# BPF.net
KiCad netlist of a schematic drawn in Altium Designer
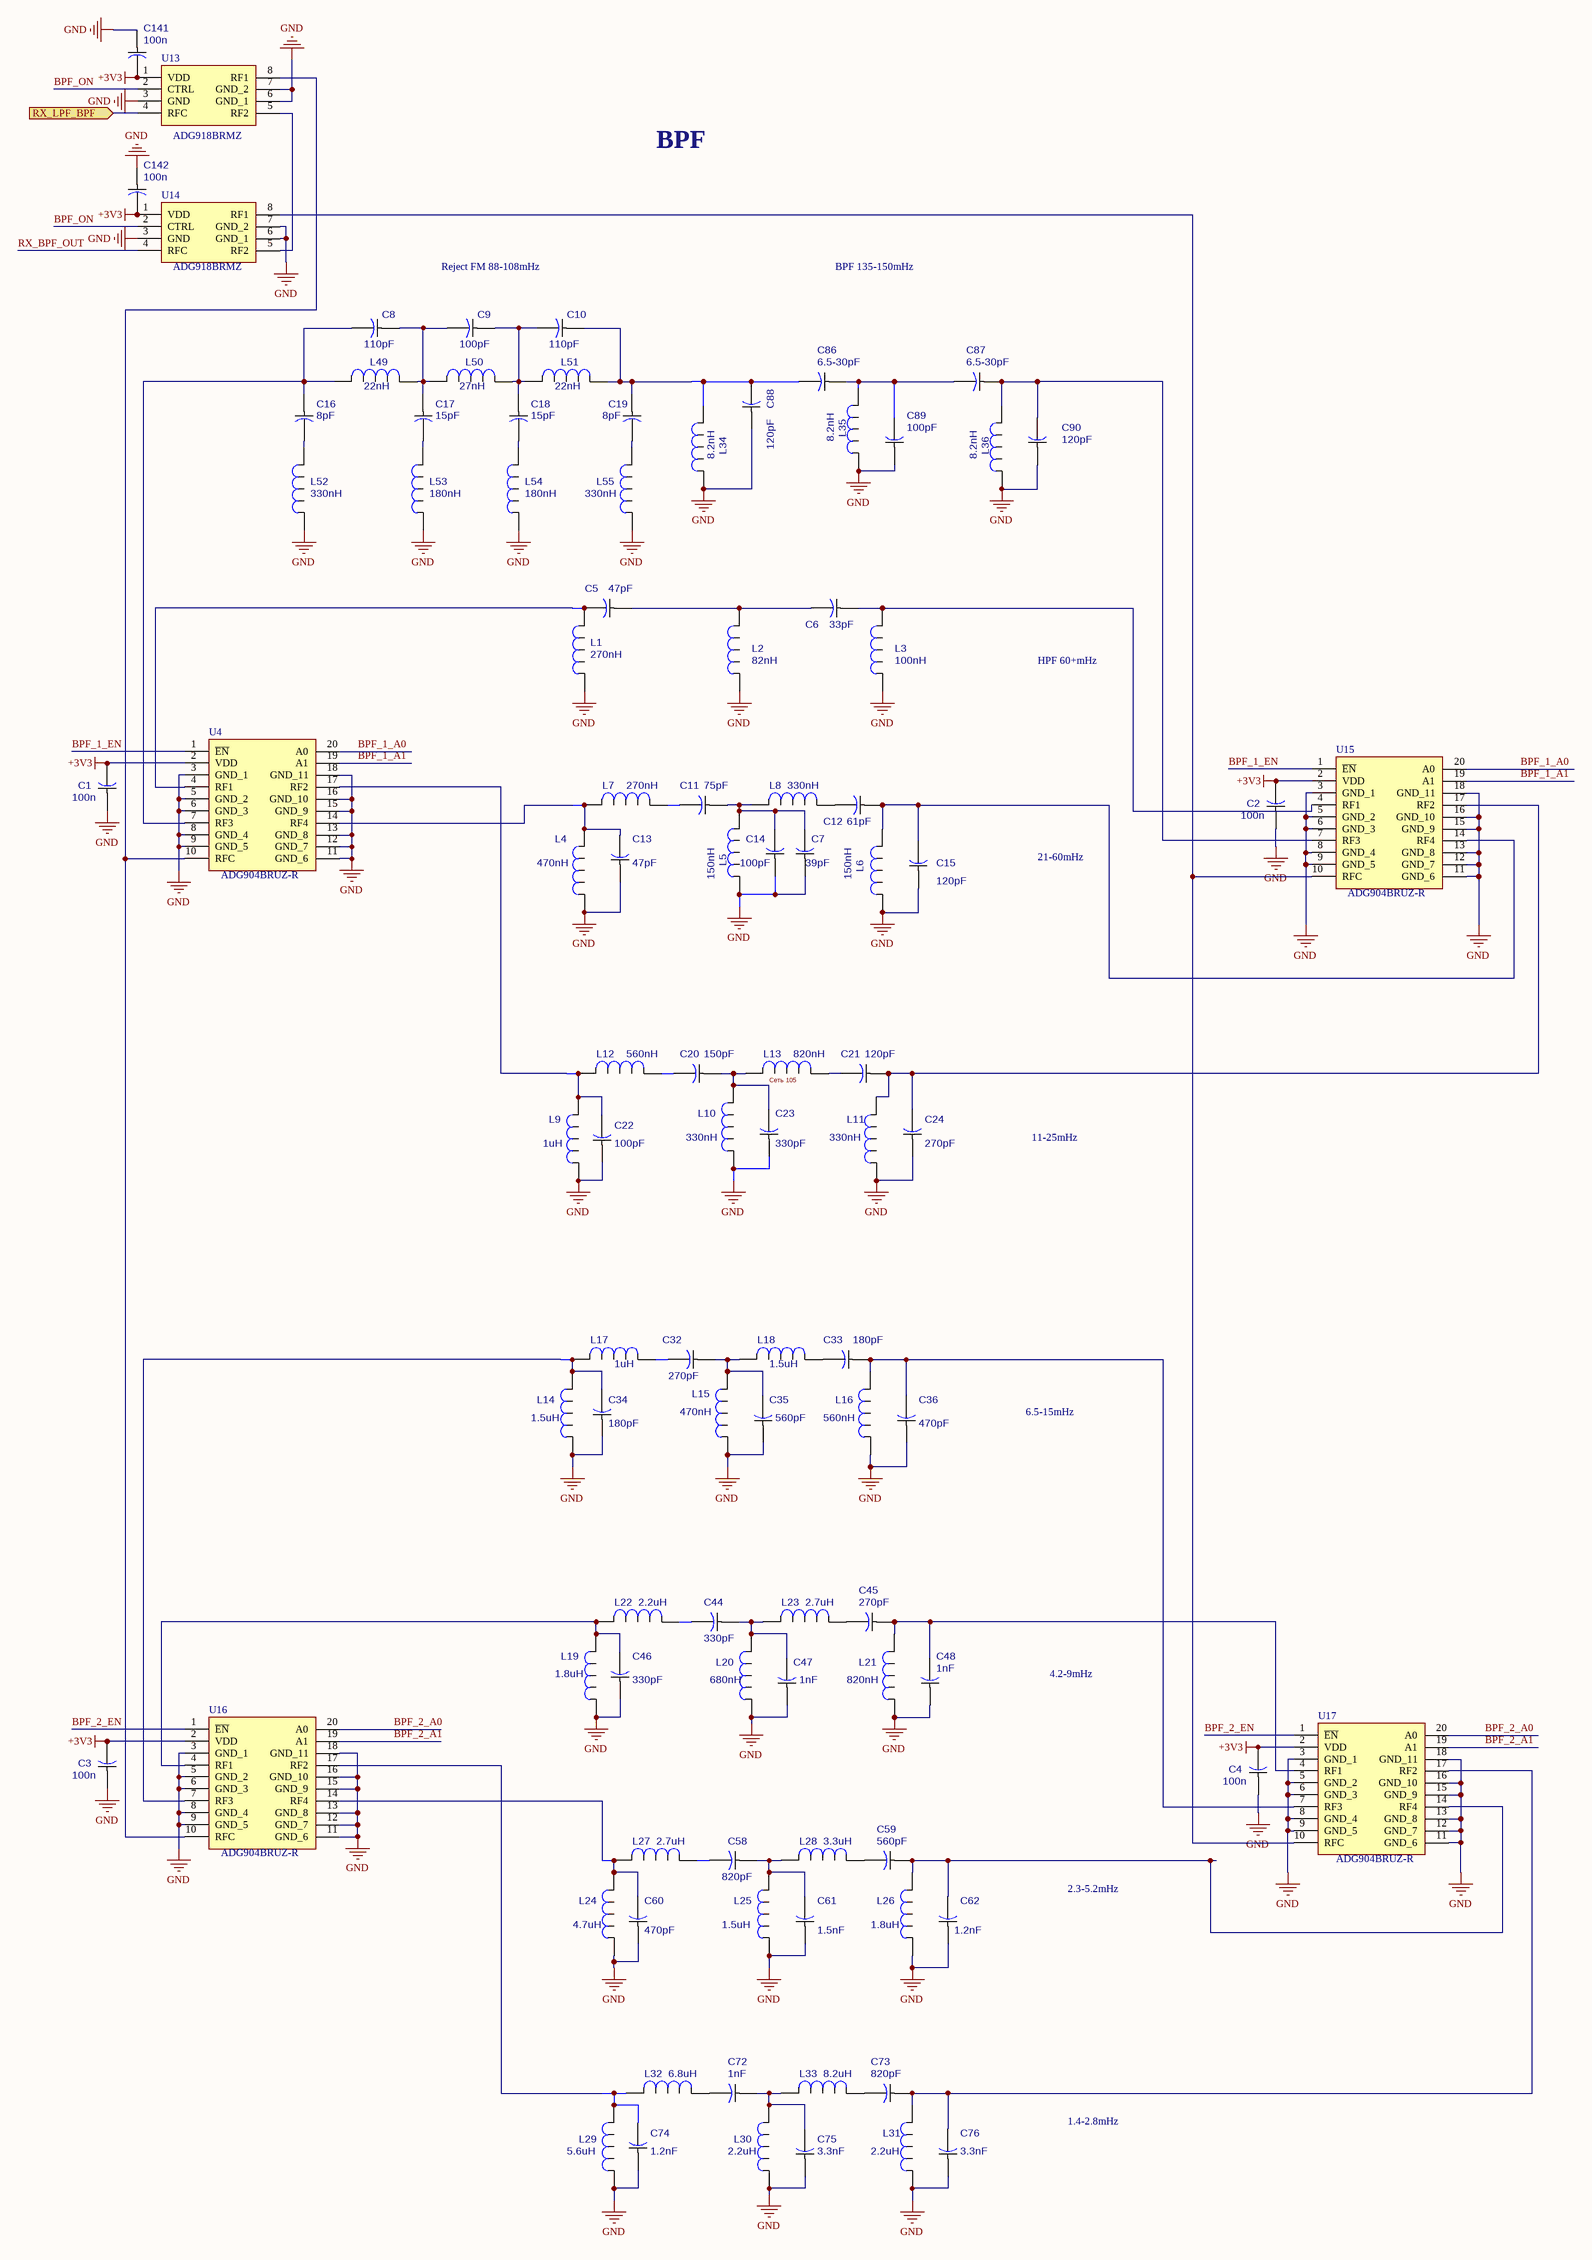
[diagram p0: BPF.SchDoc]

(export (version "E")
  (design (tool "Eeschema 10.0.6"))
  (components
    (comp (ref "C1")
      (value "100n")
      (footprint "CAP_0805")
      (description "CAP_0805")
      (libsource (lib "*") (part "CAP_0805"))
    )
    (comp (ref "C2")
      (value "100n")
      (footprint "CAP_0805")
      (description "CAP_0805")
      (libsource (lib "*") (part "CAP_0805"))
    )
    (comp (ref "C3")
      (value "100n")
      (footprint "CAP_0805")
      (description "CAP_0805")
      (libsource (lib "*") (part "CAP_0805"))
    )
    (comp (ref "C4")
      (value "100n")
      (footprint "CAP_0805")
      (description "CAP_0805")
      (libsource (lib "*") (part "CAP_0805"))
    )
    (comp (ref "C5")
      (value "47pF")
      (footprint "CAP_0805")
      (description "CAP_0805")
      (libsource (lib "*") (part "CAP_0805"))
    )
    (comp (ref "C6")
      (value "33pF")
      (footprint "CAP_0805")
      (description "CAP_0805")
      (libsource (lib "*") (part "CAP_0805"))
    )
    (comp (ref "C7")
      (value "39pF")
      (footprint "CAP_0805")
      (description "CAP_0805")
      (libsource (lib "*") (part "CAP_0805"))
    )
    (comp (ref "C8")
      (value "110pF")
      (footprint "CAP_0805")
      (description "CAP_0805")
      (libsource (lib "*") (part "CAP_0805"))
    )
    (comp (ref "C9")
      (value "100pF")
      (footprint "CAP_0805")
      (description "CAP_0805")
      (libsource (lib "*") (part "CAP_0805"))
    )
    (comp (ref "C10")
      (value "110pF")
      (footprint "CAP_0805")
      (description "CAP_0805")
      (libsource (lib "*") (part "CAP_0805"))
    )
    (comp (ref "C11")
      (value "75pF")
      (footprint "CAP_0805")
      (description "CAP_0805")
      (libsource (lib "*") (part "CAP_0805"))
    )
    (comp (ref "C12")
      (value "61pF")
      (footprint "CAP_0805")
      (description "CAP_0805")
      (libsource (lib "*") (part "CAP_0805"))
    )
    (comp (ref "C13")
      (value "47pF")
      (footprint "CAP_0805")
      (description "CAP_0805")
      (libsource (lib "*") (part "CAP_0805"))
    )
    (comp (ref "C14")
      (value "100pF")
      (footprint "CAP_0805")
      (description "CAP_0805")
      (libsource (lib "*") (part "CAP_0805"))
    )
    (comp (ref "C15")
      (value "120pF")
      (footprint "CAP_0805")
      (description "CAP_0805")
      (libsource (lib "*") (part "CAP_0805"))
    )
    (comp (ref "C16")
      (value "8pF")
      (footprint "CAP_0805")
      (description "CAP_0805")
      (libsource (lib "*") (part "CAP_0805"))
    )
    (comp (ref "C17")
      (value "15pF")
      (footprint "CAP_0805")
      (description "CAP_0805")
      (libsource (lib "*") (part "CAP_0805"))
    )
    (comp (ref "C18")
      (value "15pF")
      (footprint "CAP_0805")
      (description "CAP_0805")
      (libsource (lib "*") (part "CAP_0805"))
    )
    (comp (ref "C19")
      (value "8pF")
      (footprint "CAP_0805")
      (description "CAP_0805")
      (libsource (lib "*") (part "CAP_0805"))
    )
    (comp (ref "C20")
      (value "150pF")
      (footprint "CAP_0805")
      (description "CAP_0805")
      (libsource (lib "*") (part "CAP_0805"))
    )
    (comp (ref "C21")
      (value "120pF")
      (footprint "CAP_0805")
      (description "CAP_0805")
      (libsource (lib "*") (part "CAP_0805"))
    )
    (comp (ref "C22")
      (value "100pF")
      (footprint "CAP_0805")
      (description "CAP_0805")
      (libsource (lib "*") (part "CAP_0805"))
    )
    (comp (ref "C23")
      (value "330pF")
      (footprint "CAP_0805")
      (description "CAP_0805")
      (libsource (lib "*") (part "CAP_0805"))
    )
    (comp (ref "C24")
      (value "270pF")
      (footprint "CAP_0805")
      (description "CAP_0805")
      (libsource (lib "*") (part "CAP_0805"))
    )
    (comp (ref "C32")
      (value "270pF")
      (footprint "CAP_0805")
      (description "CAP_0805")
      (libsource (lib "*") (part "CAP_0805"))
    )
    (comp (ref "C33")
      (value "180pF")
      (footprint "CAP_0805")
      (description "CAP_0805")
      (libsource (lib "*") (part "CAP_0805"))
    )
    (comp (ref "C34")
      (value "180pF")
      (footprint "CAP_0805")
      (description "CAP_0805")
      (libsource (lib "*") (part "CAP_0805"))
    )
    (comp (ref "C35")
      (value "560pF")
      (footprint "CAP_0805")
      (description "CAP_0805")
      (libsource (lib "*") (part "CAP_0805"))
    )
    (comp (ref "C36")
      (value "470pF")
      (footprint "CAP_0805")
      (description "CAP_0805")
      (libsource (lib "*") (part "CAP_0805"))
    )
    (comp (ref "C44")
      (value "330pF")
      (footprint "CAP_0805")
      (description "CAP_0805")
      (libsource (lib "*") (part "CAP_0805"))
    )
    (comp (ref "C45")
      (value "270pF")
      (footprint "CAP_0805")
      (description "CAP_0805")
      (fields (field (name "Comment") "51pF"))
      (libsource (lib "*") (part "CAP_0805"))
    )
    (comp (ref "C46")
      (value "330pF")
      (footprint "CAP_0805")
      (description "CAP_0805")
      (libsource (lib "*") (part "CAP_0805"))
    )
    (comp (ref "C47")
      (value "1nF")
      (footprint "CAP_0805")
      (description "CAP_0805")
      (libsource (lib "*") (part "CAP_0805"))
    )
    (comp (ref "C48")
      (value "1nF")
      (footprint "CAP_0805")
      (description "CAP_0805")
      (libsource (lib "*") (part "CAP_0805"))
    )
    (comp (ref "C58")
      (value "820pF")
      (footprint "CAP_0805")
      (description "CAP_0805")
      (libsource (lib "*") (part "CAP_0805"))
    )
    (comp (ref "C59")
      (value "560pF")
      (footprint "CAP_0805")
      (description "CAP_0805")
      (fields (field (name "Comment") "680pF"))
      (libsource (lib "*") (part "CAP_0805"))
    )
    (comp (ref "C60")
      (value "470pF")
      (footprint "CAP_0805")
      (description "CAP_0805")
      (libsource (lib "*") (part "CAP_0805"))
    )
    (comp (ref "C61")
      (value "1.5nF")
      (footprint "CAP_0805")
      (description "CAP_0805")
      (libsource (lib "*") (part "CAP_0805"))
    )
    (comp (ref "C62")
      (value "1.2nF")
      (footprint "CAP_0805")
      (description "CAP_0805")
      (libsource (lib "*") (part "CAP_0805"))
    )
    (comp (ref "C72")
      (value "1nF")
      (footprint "CAP_0805")
      (description "CAP_0805")
      (libsource (lib "*") (part "CAP_0805"))
    )
    (comp (ref "C73")
      (value "820pF")
      (footprint "CAP_0805")
      (description "CAP_0805")
      (libsource (lib "*") (part "CAP_0805"))
    )
    (comp (ref "C74")
      (value "1.2nF")
      (footprint "CAP_0805")
      (description "CAP_0805")
      (libsource (lib "*") (part "CAP_0805"))
    )
    (comp (ref "C75")
      (value "3.3nF")
      (footprint "CAP_0805")
      (description "CAP_0805")
      (libsource (lib "*") (part "CAP_0805"))
    )
    (comp (ref "C76")
      (value "3.3nF")
      (footprint "CAP_0805")
      (description "CAP_0805")
      (libsource (lib "*") (part "CAP_0805"))
    )
    (comp (ref "C86")
      (value "6.5-30pF")
      (footprint "5025[2010]")
      (description "TZC3P300A110")
      (libsource (lib "*") (part "CAP_0805"))
    )
    (comp (ref "C87")
      (value "6.5-30pF")
      (footprint "5025[2010]")
      (description "TZC3P300A110")
      (libsource (lib "*") (part "CAP_0805"))
    )
    (comp (ref "C88")
      (value "120pF")
      (footprint "CAP_0805")
      (description "CAP_0805")
      (libsource (lib "*") (part "CAP_0805"))
    )
    (comp (ref "C89")
      (value "100pF")
      (footprint "CAP_0805")
      (description "CAP_0805")
      (libsource (lib "*") (part "CAP_0805"))
    )
    (comp (ref "C90")
      (value "120pF")
      (footprint "CAP_0805")
      (description "CAP_0805")
      (libsource (lib "*") (part "CAP_0805"))
    )
    (comp (ref "C141")
      (value "100n")
      (footprint "CAP_0805")
      (description "CAP_0805")
      (libsource (lib "*") (part "CAP_0805"))
    )
    (comp (ref "C142")
      (value "100n")
      (footprint "CAP_0805")
      (description "CAP_0805")
      (libsource (lib "*") (part "CAP_0805"))
    )
    (comp (ref "L1")
      (value "270nH")
      (footprint "IND_0805")
      (description "IND_0805")
      (libsource (lib "*") (part "IND_0805"))
    )
    (comp (ref "L2")
      (value "82nH")
      (footprint "IND_0805")
      (description "IND_0805")
      (libsource (lib "*") (part "IND_0805"))
    )
    (comp (ref "L3")
      (value "100nH")
      (footprint "IND_0805")
      (description "IND_0805")
      (libsource (lib "*") (part "IND_0805"))
    )
    (comp (ref "L4")
      (value "470nH")
      (footprint "IND_0805")
      (description "IND_0805")
      (libsource (lib "*") (part "IND_0805"))
    )
    (comp (ref "L5")
      (value "150nH")
      (footprint "IND_0805")
      (description "IND_0805")
      (libsource (lib "*") (part "IND_0805"))
    )
    (comp (ref "L6")
      (value "150nH")
      (footprint "IND_0805")
      (description "IND_0805")
      (libsource (lib "*") (part "IND_0805"))
    )
    (comp (ref "L7")
      (value "270nH")
      (footprint "IND_0805")
      (description "IND_0805")
      (libsource (lib "*") (part "IND_0805"))
    )
    (comp (ref "L8")
      (value "330nH")
      (footprint "IND_0805")
      (description "IND_0805")
      (libsource (lib "*") (part "IND_0805"))
    )
    (comp (ref "L9")
      (value "1uH")
      (footprint "IND_0805")
      (description "IND_0805")
      (libsource (lib "*") (part "IND_0805"))
    )
    (comp (ref "L10")
      (value "330nH")
      (footprint "IND_0805")
      (description "IND_0805")
      (libsource (lib "*") (part "IND_0805"))
    )
    (comp (ref "L11")
      (value "330nH")
      (footprint "IND_0805")
      (description "IND_0805")
      (libsource (lib "*") (part "IND_0805"))
    )
    (comp (ref "L12")
      (value "560nH")
      (footprint "IND_0805")
      (description "IND_0805")
      (libsource (lib "*") (part "IND_0805"))
    )
    (comp (ref "L13")
      (value "820nH")
      (footprint "IND_0805")
      (description "IND_0805")
      (libsource (lib "*") (part "IND_0805"))
    )
    (comp (ref "L14")
      (value "1.5uH")
      (footprint "IND_0805")
      (description "IND_0805")
      (libsource (lib "*") (part "IND_0805"))
    )
    (comp (ref "L15")
      (value "470nH")
      (footprint "IND_0805")
      (description "IND_0805")
      (libsource (lib "*") (part "IND_0805"))
    )
    (comp (ref "L16")
      (value "560nH")
      (footprint "IND_0805")
      (description "IND_0805")
      (libsource (lib "*") (part "IND_0805"))
    )
    (comp (ref "L17")
      (value "1uH")
      (footprint "IND_0805")
      (description "IND_0805")
      (libsource (lib "*") (part "IND_0805"))
    )
    (comp (ref "L18")
      (value "1.5uH")
      (footprint "IND_0805")
      (description "IND_0805")
      (libsource (lib "*") (part "IND_0805"))
    )
    (comp (ref "L19")
      (value "1.8uH")
      (footprint "IND_0805")
      (description "IND_0805")
      (libsource (lib "*") (part "IND_0805"))
    )
    (comp (ref "L20")
      (value "680nH")
      (footprint "IND_0805")
      (description "IND_0805")
      (libsource (lib "*") (part "IND_0805"))
    )
    (comp (ref "L21")
      (value "820nH")
      (footprint "IND_0805")
      (description "IND_0805")
      (libsource (lib "*") (part "IND_0805"))
    )
    (comp (ref "L22")
      (value "2.2uH")
      (footprint "IND_0805")
      (description "IND_0805")
      (libsource (lib "*") (part "IND_0805"))
    )
    (comp (ref "L23")
      (value "2.7uH")
      (footprint "IND_0805")
      (description "IND_0805")
      (libsource (lib "*") (part "IND_0805"))
    )
    (comp (ref "L24")
      (value "4.7uH")
      (footprint "IND_0805")
      (description "IND_0805")
      (libsource (lib "*") (part "IND_0805"))
    )
    (comp (ref "L25")
      (value "1.5uH")
      (footprint "IND_0805")
      (description "IND_0805")
      (libsource (lib "*") (part "IND_0805"))
    )
    (comp (ref "L26")
      (value "1.8uH")
      (footprint "IND_0805")
      (description "IND_0805")
      (libsource (lib "*") (part "IND_0805"))
    )
    (comp (ref "L27")
      (value "2.7uH")
      (footprint "IND_0805")
      (description "IND_0805")
      (libsource (lib "*") (part "IND_0805"))
    )
    (comp (ref "L28")
      (value "3.3uH")
      (footprint "IND_0805")
      (description "IND_0805")
      (libsource (lib "*") (part "IND_0805"))
    )
    (comp (ref "L29")
      (value "5.6uH")
      (footprint "IND_0805")
      (description "IND_0805")
      (libsource (lib "*") (part "IND_0805"))
    )
    (comp (ref "L30")
      (value "2.2uH")
      (footprint "IND_0805")
      (description "IND_0805")
      (libsource (lib "*") (part "IND_0805"))
    )
    (comp (ref "L31")
      (value "2.2uH")
      (footprint "IND_0805")
      (description "IND_0805")
      (libsource (lib "*") (part "IND_0805"))
    )
    (comp (ref "L32")
      (value "6.8uH")
      (footprint "IND_0805")
      (description "IND_0805")
      (libsource (lib "*") (part "IND_0805"))
    )
    (comp (ref "L33")
      (value "8.2uH")
      (footprint "IND_0805")
      (description "IND_0805")
      (libsource (lib "*") (part "IND_0805"))
    )
    (comp (ref "L34")
      (value "8.2nH")
      (footprint "IND_0805")
      (description "IND_0805")
      (libsource (lib "*") (part "IND_0805"))
    )
    (comp (ref "L35")
      (value "8.2nH")
      (footprint "IND_0805")
      (description "IND_0805")
      (libsource (lib "*") (part "IND_0805"))
    )
    (comp (ref "L36")
      (value "8.2nH")
      (footprint "IND_0805")
      (description "IND_0805")
      (libsource (lib "*") (part "IND_0805"))
    )
    (comp (ref "L49")
      (value "22nH")
      (footprint "IND_0805")
      (description "IND_0805")
      (libsource (lib "*") (part "IND_0805"))
    )
    (comp (ref "L50")
      (value "27nH")
      (footprint "IND_0805")
      (description "IND_0805")
      (libsource (lib "*") (part "IND_0805"))
    )
    (comp (ref "L51")
      (value "22nH")
      (footprint "IND_0805")
      (description "IND_0805")
      (libsource (lib "*") (part "IND_0805"))
    )
    (comp (ref "L52")
      (value "330nH")
      (footprint "IND_0805")
      (description "IND_0805")
      (libsource (lib "*") (part "IND_0805"))
    )
    (comp (ref "L53")
      (value "180nH")
      (footprint "IND_0805")
      (description "IND_0805")
      (libsource (lib "*") (part "IND_0805"))
    )
    (comp (ref "L54")
      (value "180nH")
      (footprint "IND_0805")
      (description "IND_0805")
      (libsource (lib "*") (part "IND_0805"))
    )
    (comp (ref "L55")
      (value "330nH")
      (footprint "IND_0805")
      (description "IND_0805")
      (libsource (lib "*") (part "IND_0805"))
    )
    (comp (ref "U4")
      (value "ADG904BRUZ-R")
      (footprint "SamacSys:SOP65P640X120-20N")
      (description "Integrated Circuit")
      (fields
        (field (name "MOUSER PART NUMBER") "584-ADG904BRUZ-R")
        (field (name "RS PART NUMBER") "5385019P")
      )
      (libsource (lib "*") (part "ADG904BRUZ-R"))
    )
    (comp (ref "U13")
      (value "ADG918BRMZ")
      (footprint "SamacSys:SOP65P490X110-8N")
      (description "Integrated Circuit")
      (fields (field (name "MOUSER PART NUMBER") "584-ADG918BRMZ") (field (name "RS PART NUMBER") "4969212P"))
      (libsource (lib "*") (part "ADG918BRMZ"))
    )
    (comp (ref "U14")
      (value "ADG918BRMZ")
      (footprint "SamacSys:SOP65P490X110-8N")
      (description "Integrated Circuit")
      (fields (field (name "MOUSER PART NUMBER") "584-ADG918BRMZ") (field (name "RS PART NUMBER") "4969212P"))
      (libsource (lib "*") (part "ADG918BRMZ"))
    )
    (comp (ref "U15")
      (value "ADG904BRUZ-R")
      (footprint "SamacSys:SOP65P640X120-20N")
      (description "Integrated Circuit")
      (fields
        (field (name "MOUSER PART NUMBER") "584-ADG904BRUZ-R")
        (field (name "RS PART NUMBER") "5385019P")
      )
      (libsource (lib "*") (part "ADG904BRUZ-R"))
    )
    (comp (ref "U16")
      (value "ADG904BRUZ-R")
      (footprint "SamacSys:SOP65P640X120-20N")
      (description "Integrated Circuit")
      (fields
        (field (name "MOUSER PART NUMBER") "584-ADG904BRUZ-R")
        (field (name "RS PART NUMBER") "5385019P")
      )
      (libsource (lib "*") (part "ADG904BRUZ-R"))
    )
    (comp (ref "U17")
      (value "ADG904BRUZ-R")
      (footprint "SamacSys:SOP65P640X120-20N")
      (description "Integrated Circuit")
      (fields
        (field (name "MOUSER PART NUMBER") "584-ADG904BRUZ-R")
        (field (name "RS PART NUMBER") "5385019P")
      )
      (libsource (lib "*") (part "ADG904BRUZ-R"))
    )
  )
  (nets
    (net (code "1") (name "+3V3") (class "Default")
      (node (ref "C1") (pin "2") (pinfunction "2_2") (pintype "passive"))
      (node (ref "C141") (pin "2") (pinfunction "2_2") (pintype "passive"))
      (node (ref "C142") (pin "2") (pinfunction "2_2") (pintype "passive"))
      (node (ref "C2") (pin "2") (pinfunction "2_2") (pintype "passive"))
      (node (ref "C3") (pin "2") (pinfunction "2_2") (pintype "passive"))
      (node (ref "C4") (pin "2") (pinfunction "2_2") (pintype "passive"))
      (node (ref "U13") (pin "1") (pinfunction "VDD_1") (pintype "power_in"))
      (node (ref "U14") (pin "1") (pinfunction "VDD_1") (pintype "power_in"))
      (node (ref "U15") (pin "2") (pinfunction "VDD_2") (pintype "passive"))
      (node (ref "U16") (pin "2") (pinfunction "VDD_2") (pintype "passive"))
      (node (ref "U17") (pin "2") (pinfunction "VDD_2") (pintype "passive"))
      (node (ref "U4") (pin "2") (pinfunction "VDD_2") (pintype "passive"))
    )
    (net (code "2") (name "/BPF_1_A0") (class "Default")
      (node (ref "U15") (pin "20") (pinfunction "A0_20") (pintype "passive"))
      (node (ref "U4") (pin "20") (pinfunction "A0_20") (pintype "passive"))
    )
    (net (code "3") (name "/BPF_1_A1") (class "Default")
      (node (ref "U15") (pin "19") (pinfunction "A1_19") (pintype "passive"))
      (node (ref "U4") (pin "19") (pinfunction "A1_19") (pintype "passive"))
    )
    (net (code "4") (name "/BPF_1_EN") (class "Default")
      (node (ref "U15") (pin "1") (pinfunction "~{EN}_1") (pintype "passive"))
      (node (ref "U4") (pin "1") (pinfunction "~{EN}_1") (pintype "passive"))
    )
    (net (code "5") (name "/BPF_2_A0") (class "Default")
      (node (ref "U16") (pin "20") (pinfunction "A0_20") (pintype "passive"))
      (node (ref "U17") (pin "20") (pinfunction "A0_20") (pintype "passive"))
    )
    (net (code "6") (name "/BPF_2_A1") (class "Default")
      (node (ref "U16") (pin "19") (pinfunction "A1_19") (pintype "passive"))
      (node (ref "U17") (pin "19") (pinfunction "A1_19") (pintype "passive"))
    )
    (net (code "7") (name "/BPF_2_EN") (class "Default")
      (node (ref "U16") (pin "1") (pinfunction "~{EN}_1") (pintype "passive"))
      (node (ref "U17") (pin "1") (pinfunction "~{EN}_1") (pintype "passive"))
    )
    (net (code "8") (name "/BPF_ON") (class "Default")
      (node (ref "U13") (pin "2") (pinfunction "CTRL_2") (pintype "passive"))
      (node (ref "U14") (pin "2") (pinfunction "CTRL_2") (pintype "passive"))
    )
    (net (code "9") (name "/RX_BPF_OUT") (class "Default")
      (node (ref "U14") (pin "4") (pinfunction "RFC_4") (pintype "passive"))
    )
    (net (code "10") (name "/RX_LPF_BPF") (class "Default")
      (node (ref "U13") (pin "4") (pinfunction "RFC_4") (pintype "passive"))
    )
    (net (code "11") (name "/Сеть 105") (class "Default")
      (node (ref "C20") (pin "1") (pinfunction "1_1") (pintype "passive"))
      (node (ref "C23") (pin "2") (pinfunction "2_2") (pintype "passive"))
      (node (ref "L10") (pin "2") (pinfunction "2_2") (pintype "passive"))
      (node (ref "L13") (pin "1") (pinfunction "1_1") (pintype "passive"))
    )
    (net (code "12") (name "GND") (class "Default")
      (node (ref "C1") (pin "1") (pinfunction "1_1") (pintype "passive"))
      (node (ref "C13") (pin "1") (pinfunction "1_1") (pintype "passive"))
      (node (ref "C14") (pin "1") (pinfunction "1_1") (pintype "passive"))
      (node (ref "C141") (pin "1") (pinfunction "1_1") (pintype "passive"))
      (node (ref "C142") (pin "1") (pinfunction "1_1") (pintype "passive"))
      (node (ref "C15") (pin "1") (pinfunction "1_1") (pintype "passive"))
      (node (ref "C2") (pin "1") (pinfunction "1_1") (pintype "passive"))
      (node (ref "C22") (pin "1") (pinfunction "1_1") (pintype "passive"))
      (node (ref "C23") (pin "1") (pinfunction "1_1") (pintype "passive"))
      (node (ref "C24") (pin "1") (pinfunction "1_1") (pintype "passive"))
      (node (ref "C3") (pin "1") (pinfunction "1_1") (pintype "passive"))
      (node (ref "C34") (pin "1") (pinfunction "1_1") (pintype "passive"))
      (node (ref "C35") (pin "1") (pinfunction "1_1") (pintype "passive"))
      (node (ref "C36") (pin "1") (pinfunction "1_1") (pintype "passive"))
      (node (ref "C4") (pin "1") (pinfunction "1_1") (pintype "passive"))
      (node (ref "C46") (pin "1") (pinfunction "1_1") (pintype "passive"))
      (node (ref "C47") (pin "1") (pinfunction "1_1") (pintype "passive"))
      (node (ref "C48") (pin "1") (pinfunction "1_1") (pintype "passive"))
      (node (ref "C60") (pin "1") (pinfunction "1_1") (pintype "passive"))
      (node (ref "C61") (pin "1") (pinfunction "1_1") (pintype "passive"))
      (node (ref "C62") (pin "1") (pinfunction "1_1") (pintype "passive"))
      (node (ref "C7") (pin "1") (pinfunction "1_1") (pintype "passive"))
      (node (ref "C74") (pin "1") (pinfunction "1_1") (pintype "passive"))
      (node (ref "C75") (pin "1") (pinfunction "1_1") (pintype "passive"))
      (node (ref "C76") (pin "1") (pinfunction "1_1") (pintype "passive"))
      (node (ref "C88") (pin "1") (pinfunction "1_1") (pintype "passive"))
      (node (ref "C89") (pin "1") (pinfunction "1_1") (pintype "passive"))
      (node (ref "C90") (pin "1") (pinfunction "1_1") (pintype "passive"))
      (node (ref "L1") (pin "1") (pinfunction "1_1") (pintype "passive"))
      (node (ref "L10") (pin "1") (pinfunction "1_1") (pintype "passive"))
      (node (ref "L11") (pin "1") (pinfunction "1_1") (pintype "passive"))
      (node (ref "L14") (pin "1") (pinfunction "1_1") (pintype "passive"))
      (node (ref "L15") (pin "1") (pinfunction "1_1") (pintype "passive"))
      (node (ref "L16") (pin "1") (pinfunction "1_1") (pintype "passive"))
      (node (ref "L19") (pin "1") (pinfunction "1_1") (pintype "passive"))
      (node (ref "L2") (pin "1") (pinfunction "1_1") (pintype "passive"))
      (node (ref "L20") (pin "1") (pinfunction "1_1") (pintype "passive"))
      (node (ref "L21") (pin "1") (pinfunction "1_1") (pintype "passive"))
      (node (ref "L24") (pin "1") (pinfunction "1_1") (pintype "passive"))
      (node (ref "L25") (pin "1") (pinfunction "1_1") (pintype "passive"))
      (node (ref "L26") (pin "1") (pinfunction "1_1") (pintype "passive"))
      (node (ref "L29") (pin "1") (pinfunction "1_1") (pintype "passive"))
      (node (ref "L3") (pin "1") (pinfunction "1_1") (pintype "passive"))
      (node (ref "L30") (pin "1") (pinfunction "1_1") (pintype "passive"))
      (node (ref "L31") (pin "1") (pinfunction "1_1") (pintype "passive"))
      (node (ref "L34") (pin "1") (pinfunction "1_1") (pintype "passive"))
      (node (ref "L35") (pin "1") (pinfunction "1_1") (pintype "passive"))
      (node (ref "L36") (pin "1") (pinfunction "1_1") (pintype "passive"))
      (node (ref "L4") (pin "1") (pinfunction "1_1") (pintype "passive"))
      (node (ref "L5") (pin "1") (pinfunction "1_1") (pintype "passive"))
      (node (ref "L52") (pin "1") (pinfunction "1_1") (pintype "passive"))
      (node (ref "L53") (pin "1") (pinfunction "1_1") (pintype "passive"))
      (node (ref "L54") (pin "1") (pinfunction "1_1") (pintype "passive"))
      (node (ref "L55") (pin "1") (pinfunction "1_1") (pintype "passive"))
      (node (ref "L6") (pin "1") (pinfunction "1_1") (pintype "passive"))
      (node (ref "L9") (pin "1") (pinfunction "1_1") (pintype "passive"))
      (node (ref "U13") (pin "3") (pinfunction "GND_3") (pintype "power_in"))
      (node (ref "U13") (pin "6") (pinfunction "GND_1_6") (pintype "power_in"))
      (node (ref "U13") (pin "7") (pinfunction "GND_2_7") (pintype "power_in"))
      (node (ref "U14") (pin "3") (pinfunction "GND_3") (pintype "power_in"))
      (node (ref "U14") (pin "6") (pinfunction "GND_1_6") (pintype "power_in"))
      (node (ref "U14") (pin "7") (pinfunction "GND_2_7") (pintype "power_in"))
      (node (ref "U15") (pin "11") (pinfunction "GND_6_11") (pintype "passive"))
      (node (ref "U15") (pin "12") (pinfunction "GND_7_12") (pintype "passive"))
      (node (ref "U15") (pin "13") (pinfunction "GND_8_13") (pintype "passive"))
      (node (ref "U15") (pin "15") (pinfunction "GND_9_15") (pintype "passive"))
      (node (ref "U15") (pin "16") (pinfunction "GND_10_16") (pintype "passive"))
      (node (ref "U15") (pin "18") (pinfunction "GND_11_18") (pintype "passive"))
      (node (ref "U15") (pin "3") (pinfunction "GND_1_3") (pintype "passive"))
      (node (ref "U15") (pin "5") (pinfunction "GND_2_5") (pintype "passive"))
      (node (ref "U15") (pin "6") (pinfunction "GND_3_6") (pintype "passive"))
      (node (ref "U15") (pin "8") (pinfunction "GND_4_8") (pintype "passive"))
      (node (ref "U15") (pin "9") (pinfunction "GND_5_9") (pintype "passive"))
      (node (ref "U16") (pin "11") (pinfunction "GND_6_11") (pintype "passive"))
      (node (ref "U16") (pin "12") (pinfunction "GND_7_12") (pintype "passive"))
      (node (ref "U16") (pin "13") (pinfunction "GND_8_13") (pintype "passive"))
      (node (ref "U16") (pin "15") (pinfunction "GND_9_15") (pintype "passive"))
      (node (ref "U16") (pin "16") (pinfunction "GND_10_16") (pintype "passive"))
      (node (ref "U16") (pin "18") (pinfunction "GND_11_18") (pintype "passive"))
      (node (ref "U16") (pin "3") (pinfunction "GND_1_3") (pintype "passive"))
      (node (ref "U16") (pin "5") (pinfunction "GND_2_5") (pintype "passive"))
      (node (ref "U16") (pin "6") (pinfunction "GND_3_6") (pintype "passive"))
      (node (ref "U16") (pin "8") (pinfunction "GND_4_8") (pintype "passive"))
      (node (ref "U16") (pin "9") (pinfunction "GND_5_9") (pintype "passive"))
      (node (ref "U17") (pin "11") (pinfunction "GND_6_11") (pintype "passive"))
      (node (ref "U17") (pin "12") (pinfunction "GND_7_12") (pintype "passive"))
      (node (ref "U17") (pin "13") (pinfunction "GND_8_13") (pintype "passive"))
      (node (ref "U17") (pin "15") (pinfunction "GND_9_15") (pintype "passive"))
      (node (ref "U17") (pin "16") (pinfunction "GND_10_16") (pintype "passive"))
      (node (ref "U17") (pin "18") (pinfunction "GND_11_18") (pintype "passive"))
      (node (ref "U17") (pin "3") (pinfunction "GND_1_3") (pintype "passive"))
      (node (ref "U17") (pin "5") (pinfunction "GND_2_5") (pintype "passive"))
      (node (ref "U17") (pin "6") (pinfunction "GND_3_6") (pintype "passive"))
      (node (ref "U17") (pin "8") (pinfunction "GND_4_8") (pintype "passive"))
      (node (ref "U17") (pin "9") (pinfunction "GND_5_9") (pintype "passive"))
      (node (ref "U4") (pin "11") (pinfunction "GND_6_11") (pintype "passive"))
      (node (ref "U4") (pin "12") (pinfunction "GND_7_12") (pintype "passive"))
      (node (ref "U4") (pin "13") (pinfunction "GND_8_13") (pintype "passive"))
      (node (ref "U4") (pin "15") (pinfunction "GND_9_15") (pintype "passive"))
      (node (ref "U4") (pin "16") (pinfunction "GND_10_16") (pintype "passive"))
      (node (ref "U4") (pin "18") (pinfunction "GND_11_18") (pintype "passive"))
      (node (ref "U4") (pin "3") (pinfunction "GND_1_3") (pintype "passive"))
      (node (ref "U4") (pin "5") (pinfunction "GND_2_5") (pintype "passive"))
      (node (ref "U4") (pin "6") (pinfunction "GND_3_6") (pintype "passive"))
      (node (ref "U4") (pin "8") (pinfunction "GND_4_8") (pintype "passive"))
      (node (ref "U4") (pin "9") (pinfunction "GND_5_9") (pintype "passive"))
    )
    (net (code "13") (name "Net-(C5-Pad1)") (class "Default")
      (node (ref "C5") (pin "1") (pinfunction "1_1") (pintype "passive"))
      (node (ref "C6") (pin "2") (pinfunction "2_2") (pintype "passive"))
      (node (ref "L2") (pin "2") (pinfunction "2_2") (pintype "passive"))
    )
    (net (code "14") (name "Net-(C10-Pad1)") (class "Default")
      (node (ref "C10") (pin "1") (pinfunction "1_1") (pintype "passive"))
      (node (ref "C19") (pin "1") (pinfunction "1_1") (pintype "passive"))
      (node (ref "C86") (pin "2") (pinfunction "2_2") (pintype "passive"))
      (node (ref "C88") (pin "2") (pinfunction "2_2") (pintype "passive"))
      (node (ref "L34") (pin "2") (pinfunction "2_2") (pintype "passive"))
      (node (ref "L51") (pin "2") (pinfunction "2_2") (pintype "passive"))
    )
    (net (code "15") (name "Net-(C10-Pad2)") (class "Default")
      (node (ref "C10") (pin "2") (pinfunction "2_2") (pintype "passive"))
      (node (ref "C18") (pin "1") (pinfunction "1_1") (pintype "passive"))
      (node (ref "C9") (pin "1") (pinfunction "1_1") (pintype "passive"))
      (node (ref "L50") (pin "2") (pinfunction "2_2") (pintype "passive"))
      (node (ref "L51") (pin "1") (pinfunction "1_1") (pintype "passive"))
    )
    (net (code "16") (name "Net-(C11-Pad1)") (class "Default")
      (node (ref "C11") (pin "1") (pinfunction "1_1") (pintype "passive"))
      (node (ref "C14") (pin "2") (pinfunction "2_2") (pintype "passive"))
      (node (ref "C7") (pin "2") (pinfunction "2_2") (pintype "passive"))
      (node (ref "L5") (pin "2") (pinfunction "2_2") (pintype "passive"))
      (node (ref "L8") (pin "1") (pinfunction "1_1") (pintype "passive"))
    )
    (net (code "17") (name "Net-(C11-Pad2)") (class "Default")
      (node (ref "C11") (pin "2") (pinfunction "2_2") (pintype "passive"))
      (node (ref "L7") (pin "2") (pinfunction "2_2") (pintype "passive"))
    )
    (net (code "18") (name "Net-(C12-Pad2)") (class "Default")
      (node (ref "C12") (pin "2") (pinfunction "2_2") (pintype "passive"))
      (node (ref "L8") (pin "2") (pinfunction "2_2") (pintype "passive"))
    )
    (net (code "19") (name "Net-(C16-Pad2)") (class "Default")
      (node (ref "C16") (pin "2") (pinfunction "2_2") (pintype "passive"))
      (node (ref "L52") (pin "2") (pinfunction "2_2") (pintype "passive"))
    )
    (net (code "20") (name "Net-(C17-Pad1)") (class "Default")
      (node (ref "C17") (pin "1") (pinfunction "1_1") (pintype "passive"))
      (node (ref "C8") (pin "1") (pinfunction "1_1") (pintype "passive"))
      (node (ref "C9") (pin "2") (pinfunction "2_2") (pintype "passive"))
      (node (ref "L49") (pin "2") (pinfunction "2_2") (pintype "passive"))
      (node (ref "L50") (pin "1") (pinfunction "1_1") (pintype "passive"))
    )
    (net (code "21") (name "Net-(C17-Pad2)") (class "Default")
      (node (ref "C17") (pin "2") (pinfunction "2_2") (pintype "passive"))
      (node (ref "L53") (pin "2") (pinfunction "2_2") (pintype "passive"))
    )
    (net (code "22") (name "Net-(C18-Pad2)") (class "Default")
      (node (ref "C18") (pin "2") (pinfunction "2_2") (pintype "passive"))
      (node (ref "L54") (pin "2") (pinfunction "2_2") (pintype "passive"))
    )
    (net (code "23") (name "Net-(C19-Pad2)") (class "Default")
      (node (ref "C19") (pin "2") (pinfunction "2_2") (pintype "passive"))
      (node (ref "L55") (pin "2") (pinfunction "2_2") (pintype "passive"))
    )
    (net (code "24") (name "Net-(C20-Pad2)") (class "Default")
      (node (ref "C20") (pin "2") (pinfunction "2_2") (pintype "passive"))
      (node (ref "L12") (pin "2") (pinfunction "2_2") (pintype "passive"))
    )
    (net (code "25") (name "Net-(C21-Pad2)") (class "Default")
      (node (ref "C21") (pin "2") (pinfunction "2_2") (pintype "passive"))
      (node (ref "L13") (pin "2") (pinfunction "2_2") (pintype "passive"))
    )
    (net (code "26") (name "Net-(C32-Pad1)") (class "Default")
      (node (ref "C32") (pin "1") (pinfunction "1_1") (pintype "passive"))
      (node (ref "C35") (pin "2") (pinfunction "2_2") (pintype "passive"))
      (node (ref "L15") (pin "2") (pinfunction "2_2") (pintype "passive"))
      (node (ref "L18") (pin "1") (pinfunction "1_1") (pintype "passive"))
    )
    (net (code "27") (name "Net-(C32-Pad2)") (class "Default")
      (node (ref "C32") (pin "2") (pinfunction "2_2") (pintype "passive"))
      (node (ref "L17") (pin "2") (pinfunction "2_2") (pintype "passive"))
    )
    (net (code "28") (name "Net-(C33-Pad2)") (class "Default")
      (node (ref "C33") (pin "2") (pinfunction "2_2") (pintype "passive"))
      (node (ref "L18") (pin "2") (pinfunction "2_2") (pintype "passive"))
    )
    (net (code "29") (name "Net-(C44-Pad1)") (class "Default")
      (node (ref "C44") (pin "1") (pinfunction "1_1") (pintype "passive"))
      (node (ref "C47") (pin "2") (pinfunction "2_2") (pintype "passive"))
      (node (ref "L20") (pin "2") (pinfunction "2_2") (pintype "passive"))
      (node (ref "L23") (pin "1") (pinfunction "1_1") (pintype "passive"))
    )
    (net (code "30") (name "Net-(C44-Pad2)") (class "Default")
      (node (ref "C44") (pin "2") (pinfunction "2_2") (pintype "passive"))
      (node (ref "L22") (pin "2") (pinfunction "2_2") (pintype "passive"))
    )
    (net (code "31") (name "Net-(C45-Pad2)") (class "Default")
      (node (ref "C45") (pin "2") (pinfunction "2_2") (pintype "passive"))
      (node (ref "L23") (pin "2") (pinfunction "2_2") (pintype "passive"))
    )
    (net (code "32") (name "Net-(C58-Pad1)") (class "Default")
      (node (ref "C58") (pin "1") (pinfunction "1_1") (pintype "passive"))
      (node (ref "C61") (pin "2") (pinfunction "2_2") (pintype "passive"))
      (node (ref "L25") (pin "2") (pinfunction "2_2") (pintype "passive"))
      (node (ref "L28") (pin "1") (pinfunction "1_1") (pintype "passive"))
    )
    (net (code "33") (name "Net-(C58-Pad2)") (class "Default")
      (node (ref "C58") (pin "2") (pinfunction "2_2") (pintype "passive"))
      (node (ref "L27") (pin "2") (pinfunction "2_2") (pintype "passive"))
    )
    (net (code "34") (name "Net-(C59-Pad2)") (class "Default")
      (node (ref "C59") (pin "2") (pinfunction "2_2") (pintype "passive"))
      (node (ref "L28") (pin "2") (pinfunction "2_2") (pintype "passive"))
    )
    (net (code "35") (name "Net-(C72-Pad1)") (class "Default")
      (node (ref "C72") (pin "1") (pinfunction "1_1") (pintype "passive"))
      (node (ref "C75") (pin "2") (pinfunction "2_2") (pintype "passive"))
      (node (ref "L30") (pin "2") (pinfunction "2_2") (pintype "passive"))
      (node (ref "L33") (pin "1") (pinfunction "1_1") (pintype "passive"))
    )
    (net (code "36") (name "Net-(C72-Pad2)") (class "Default")
      (node (ref "C72") (pin "2") (pinfunction "2_2") (pintype "passive"))
      (node (ref "L32") (pin "2") (pinfunction "2_2") (pintype "passive"))
    )
    (net (code "37") (name "Net-(C73-Pad2)") (class "Default")
      (node (ref "C73") (pin "2") (pinfunction "2_2") (pintype "passive"))
      (node (ref "L33") (pin "2") (pinfunction "2_2") (pintype "passive"))
    )
    (net (code "38") (name "Net-(C86-Pad1)") (class "Default")
      (node (ref "C86") (pin "1") (pinfunction "1_1") (pintype "passive"))
      (node (ref "C87") (pin "2") (pinfunction "2_2") (pintype "passive"))
      (node (ref "C89") (pin "2") (pinfunction "2_2") (pintype "passive"))
      (node (ref "L35") (pin "2") (pinfunction "2_2") (pintype "passive"))
    )
    (net (code "39") (name "Net-(U4-RF1)") (class "Default")
      (node (ref "C5") (pin "2") (pinfunction "2_2") (pintype "passive"))
      (node (ref "L1") (pin "2") (pinfunction "2_2") (pintype "passive"))
      (node (ref "U4") (pin "4") (pinfunction "RF1_4") (pintype "passive"))
    )
    (net (code "40") (name "Net-(U4-RF2)") (class "Default")
      (node (ref "C22") (pin "2") (pinfunction "2_2") (pintype "passive"))
      (node (ref "L12") (pin "1") (pinfunction "1_1") (pintype "passive"))
      (node (ref "L9") (pin "2") (pinfunction "2_2") (pintype "passive"))
      (node (ref "U4") (pin "17") (pinfunction "RF2_17") (pintype "passive"))
    )
    (net (code "41") (name "Net-(U4-RF3)") (class "Default")
      (node (ref "C16") (pin "1") (pinfunction "1_1") (pintype "passive"))
      (node (ref "C8") (pin "2") (pinfunction "2_2") (pintype "passive"))
      (node (ref "L49") (pin "1") (pinfunction "1_1") (pintype "passive"))
      (node (ref "U4") (pin "7") (pinfunction "RF3_7") (pintype "passive"))
    )
    (net (code "42") (name "Net-(U4-RF4)") (class "Default")
      (node (ref "C13") (pin "2") (pinfunction "2_2") (pintype "passive"))
      (node (ref "L4") (pin "2") (pinfunction "2_2") (pintype "passive"))
      (node (ref "L7") (pin "1") (pinfunction "1_1") (pintype "passive"))
      (node (ref "U4") (pin "14") (pinfunction "RF4_14") (pintype "passive"))
    )
    (net (code "43") (name "Net-(U13-RF1)") (class "Default")
      (node (ref "U13") (pin "8") (pinfunction "RF1_8") (pintype "passive"))
      (node (ref "U16") (pin "10") (pinfunction "RFC_10") (pintype "passive"))
      (node (ref "U4") (pin "10") (pinfunction "RFC_10") (pintype "passive"))
    )
    (net (code "44") (name "Net-(U13-RF2)") (class "Default")
      (node (ref "U13") (pin "5") (pinfunction "RF2_5") (pintype "passive"))
      (node (ref "U14") (pin "5") (pinfunction "RF2_5") (pintype "passive"))
    )
    (net (code "45") (name "Net-(U14-RF1)") (class "Default")
      (node (ref "U14") (pin "8") (pinfunction "RF1_8") (pintype "passive"))
      (node (ref "U15") (pin "10") (pinfunction "RFC_10") (pintype "passive"))
      (node (ref "U17") (pin "10") (pinfunction "RFC_10") (pintype "passive"))
    )
    (net (code "46") (name "Net-(U15-RF1)") (class "Default")
      (node (ref "C6") (pin "1") (pinfunction "1_1") (pintype "passive"))
      (node (ref "L3") (pin "2") (pinfunction "2_2") (pintype "passive"))
      (node (ref "U15") (pin "4") (pinfunction "RF1_4") (pintype "passive"))
    )
    (net (code "47") (name "Net-(U15-RF2)") (class "Default")
      (node (ref "C21") (pin "1") (pinfunction "1_1") (pintype "passive"))
      (node (ref "C24") (pin "2") (pinfunction "2_2") (pintype "passive"))
      (node (ref "L11") (pin "2") (pinfunction "2_2") (pintype "passive"))
      (node (ref "U15") (pin "17") (pinfunction "RF2_17") (pintype "passive"))
    )
    (net (code "48") (name "Net-(U15-RF3)") (class "Default")
      (node (ref "C87") (pin "1") (pinfunction "1_1") (pintype "passive"))
      (node (ref "C90") (pin "2") (pinfunction "2_2") (pintype "passive"))
      (node (ref "L36") (pin "2") (pinfunction "2_2") (pintype "passive"))
      (node (ref "U15") (pin "7") (pinfunction "RF3_7") (pintype "passive"))
    )
    (net (code "49") (name "Net-(U15-RF4)") (class "Default")
      (node (ref "C12") (pin "1") (pinfunction "1_1") (pintype "passive"))
      (node (ref "C15") (pin "2") (pinfunction "2_2") (pintype "passive"))
      (node (ref "L6") (pin "2") (pinfunction "2_2") (pintype "passive"))
      (node (ref "U15") (pin "14") (pinfunction "RF4_14") (pintype "passive"))
    )
    (net (code "50") (name "Net-(U16-RF1)") (class "Default")
      (node (ref "C46") (pin "2") (pinfunction "2_2") (pintype "passive"))
      (node (ref "L19") (pin "2") (pinfunction "2_2") (pintype "passive"))
      (node (ref "L22") (pin "1") (pinfunction "1_1") (pintype "passive"))
      (node (ref "U16") (pin "4") (pinfunction "RF1_4") (pintype "passive"))
    )
    (net (code "51") (name "Net-(U16-RF2)") (class "Default")
      (node (ref "C74") (pin "2") (pinfunction "2_2") (pintype "passive"))
      (node (ref "L29") (pin "2") (pinfunction "2_2") (pintype "passive"))
      (node (ref "L32") (pin "1") (pinfunction "1_1") (pintype "passive"))
      (node (ref "U16") (pin "17") (pinfunction "RF2_17") (pintype "passive"))
    )
    (net (code "52") (name "Net-(U16-RF3)") (class "Default")
      (node (ref "C34") (pin "2") (pinfunction "2_2") (pintype "passive"))
      (node (ref "L14") (pin "2") (pinfunction "2_2") (pintype "passive"))
      (node (ref "L17") (pin "1") (pinfunction "1_1") (pintype "passive"))
      (node (ref "U16") (pin "7") (pinfunction "RF3_7") (pintype "passive"))
    )
    (net (code "53") (name "Net-(U16-RF4)") (class "Default")
      (node (ref "C60") (pin "2") (pinfunction "2_2") (pintype "passive"))
      (node (ref "L24") (pin "2") (pinfunction "2_2") (pintype "passive"))
      (node (ref "L27") (pin "1") (pinfunction "1_1") (pintype "passive"))
      (node (ref "U16") (pin "14") (pinfunction "RF4_14") (pintype "passive"))
    )
    (net (code "54") (name "Net-(U17-RF1)") (class "Default")
      (node (ref "C45") (pin "1") (pinfunction "1_1") (pintype "passive"))
      (node (ref "C48") (pin "2") (pinfunction "2_2") (pintype "passive"))
      (node (ref "L21") (pin "2") (pinfunction "2_2") (pintype "passive"))
      (node (ref "U17") (pin "4") (pinfunction "RF1_4") (pintype "passive"))
    )
    (net (code "55") (name "Net-(U17-RF2)") (class "Default")
      (node (ref "C73") (pin "1") (pinfunction "1_1") (pintype "passive"))
      (node (ref "C76") (pin "2") (pinfunction "2_2") (pintype "passive"))
      (node (ref "L31") (pin "2") (pinfunction "2_2") (pintype "passive"))
      (node (ref "U17") (pin "17") (pinfunction "RF2_17") (pintype "passive"))
    )
    (net (code "56") (name "Net-(U17-RF3)") (class "Default")
      (node (ref "C33") (pin "1") (pinfunction "1_1") (pintype "passive"))
      (node (ref "C36") (pin "2") (pinfunction "2_2") (pintype "passive"))
      (node (ref "L16") (pin "2") (pinfunction "2_2") (pintype "passive"))
      (node (ref "U17") (pin "7") (pinfunction "RF3_7") (pintype "passive"))
    )
    (net (code "57") (name "Net-(U17-RF4)") (class "Default")
      (node (ref "C59") (pin "1") (pinfunction "1_1") (pintype "passive"))
      (node (ref "C62") (pin "2") (pinfunction "2_2") (pintype "passive"))
      (node (ref "L26") (pin "2") (pinfunction "2_2") (pintype "passive"))
      (node (ref "U17") (pin "14") (pinfunction "RF4_14") (pintype "passive"))
    )
  )
)
